# MCU.net
KiCad netlist of a schematic drawn in Altium Designer
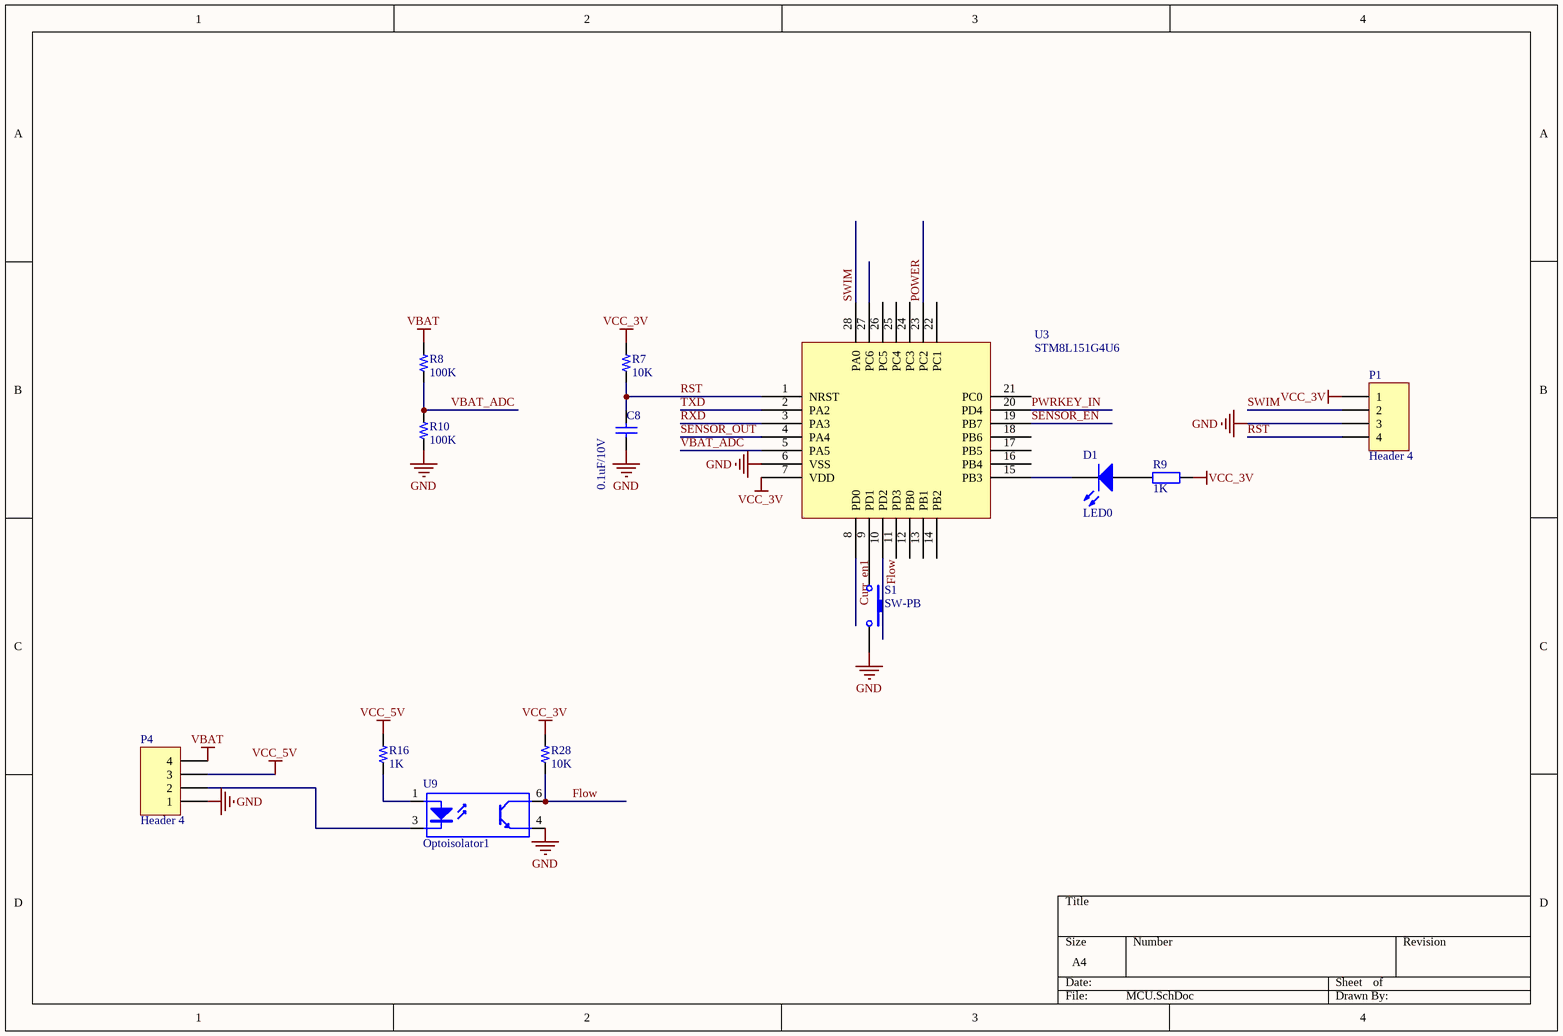
[diagram p0: MCU.SchDoc]

(export (version "E")
  (design (tool "Eeschema 10.0.6"))
  (components
    (comp (ref "C8")
      (value "0.1uF/10V")
      (footprint "0603C")
      (description "Capacitor")
      (fields (field (name "PUBLISHER") "Altium Limited"))
      (libsource (lib "Miscellaneous Devices") (part "Cap"))
    )
    (comp (ref "D1")
      (value "LED0")
      (footprint "0603LED")
      (description "Typical INFRARED GaAs LED")
      (fields (field (name "PUBLISHER") "Altium Limited"))
      (libsource (lib "Miscellaneous Devices") (part "LED0"))
    )
    (comp (ref "P1")
      (value "Header 4")
      (footprint "HDR1X4")
      (description "Header, 4-Pin")
      (fields (field (name "PUBLISHER") "Altium Limited"))
      (libsource (lib "") (part "Header 4_1"))
    )
    (comp (ref "P4")
      (value "Header 4")
      (footprint "HDR1X4")
      (description "Header, 4-Pin")
      (fields (field (name "PUBLISHER") "Altium Limited"))
      (libsource (lib "Miscellaneous Connectors") (part "Header 4"))
    )
    (comp (ref "R7") (value "10K") (footprint "0603R") (description "R") (libsource (lib "JRJ_1") (part "R")))
    (comp (ref "R8")
      (value "100K")
      (footprint "0603R")
      (description "R")
      (libsource (lib "JRJ_1") (part "R"))
    )
    (comp (ref "R9")
      (value "1K")
      (footprint "0603R")
      (description "Resistor")
      (fields (field (name "PUBLISHER") "Altium Limited"))
      (libsource (lib "Miscellaneous Devices") (part "Res2"))
    )
    (comp (ref "R10")
      (value "100K")
      (footprint "0603R")
      (description "R")
      (libsource (lib "JRJ_1") (part "R"))
    )
    (comp (ref "R16") (value "1K") (footprint "0603R") (description "R") (libsource (lib "JRJ_1") (part "R")))
    (comp (ref "R28")
      (value "10K")
      (footprint "0603R")
      (description "R")
      (libsource (lib "JRJ_1") (part "R"))
    )
    (comp (ref "S1")
      (value "SW-PB")
      (footprint "key")
      (description "Switch")
      (fields (field (name "PUBLISHER") "Altium Limited"))
      (libsource (lib "Miscellaneous Devices") (part "SW-PB"))
    )
    (comp (ref "U3")
      (value "STM8L151G4U6")
      (footprint "UFQFPN28")
      (libsource (lib "Schlib_20110825") (part "STM8L151G4U6"))
    )
    (comp (ref "U9")
      (value "Optoisolator1")
      (footprint "DIP-4")
      (description "4-Pin Phototransistor Optocoupler")
      (fields (field (name "PUBLISHER") "Altium Limited"))
      (libsource (lib "Miscellaneous Devices") (part "Optoisolator1"))
    )
  )
  (nets
    (net (code "1") (name "/Curr_en1") (class "Default")
      (node (ref "U3") (pin "8") (pinfunction "PD0_8") (pintype "passive"))
    )
    (net (code "2") (name "/Flow") (class "Default")
      (node (ref "R28") (pin "1") (pintype "passive"))
      (node (ref "U3") (pin "10") (pinfunction "PD2_10") (pintype "passive"))
      (node (ref "U9") (pin "6") (pinfunction "C_6") (pintype "passive"))
    )
    (net (code "3") (name "/POWER") (class "Default")
      (node (ref "U3") (pin "23") (pinfunction "PC2_23") (pintype "passive"))
    )
    (net (code "4") (name "/PWRKEY_IN") (class "Default")
      (node (ref "U3") (pin "20") (pinfunction "PD4_20") (pintype "passive"))
    )
    (net (code "5") (name "/RST") (class "Default")
      (node (ref "C8") (pin "1") (pinfunction "1_1") (pintype "passive"))
      (node (ref "P1") (pin "4") (pinfunction "4_4") (pintype "passive"))
      (node (ref "R7") (pin "1") (pintype "passive"))
      (node (ref "U3") (pin "1") (pinfunction "NRST_1") (pintype "passive"))
    )
    (net (code "6") (name "/RXD") (class "Default")
      (node (ref "U3") (pin "3") (pinfunction "PA3_3") (pintype "passive"))
    )
    (net (code "7") (name "/SENSOR_EN") (class "Default")
      (node (ref "U3") (pin "19") (pinfunction "PB7_19") (pintype "passive"))
    )
    (net (code "8") (name "/SENSOR_OUT") (class "Default")
      (node (ref "U3") (pin "4") (pinfunction "PA4_4") (pintype "passive"))
    )
    (net (code "9") (name "/SWIM") (class "Default")
      (node (ref "P1") (pin "2") (pinfunction "2_2") (pintype "passive"))
      (node (ref "U3") (pin "28") (pinfunction "PA0_28") (pintype "passive"))
    )
    (net (code "10") (name "/TXD") (class "Default")
      (node (ref "U3") (pin "2") (pinfunction "PA2_2") (pintype "passive"))
    )
    (net (code "11") (name "/VBAT_ADC") (class "Default")
      (node (ref "R10") (pin "2") (pintype "passive"))
      (node (ref "R8") (pin "1") (pintype "passive"))
      (node (ref "U3") (pin "5") (pinfunction "PA5_5") (pintype "passive"))
    )
    (net (code "12") (name "GND") (class "Default")
      (node (ref "C8") (pin "2") (pinfunction "2_2") (pintype "passive"))
      (node (ref "P1") (pin "3") (pinfunction "3_3") (pintype "passive"))
      (node (ref "P4") (pin "1") (pinfunction "1_1") (pintype "passive"))
      (node (ref "R10") (pin "1") (pintype "passive"))
      (node (ref "S1") (pin "2") (pinfunction "2_2") (pintype "passive"))
      (node (ref "U3") (pin "6") (pinfunction "VSS_6") (pintype "passive"))
      (node (ref "U9") (pin "4") (pinfunction "E_4") (pintype "passive"))
    )
    (net (code "13") (name "Net-(D1-A)") (class "Default")
      (node (ref "D1") (pin "1") (pinfunction "A_1") (pintype "passive"))
      (node (ref "R9") (pin "2") (pinfunction "2_2") (pintype "passive"))
    )
    (net (code "14") (name "Net-(D1-K)") (class "Default")
      (node (ref "D1") (pin "2") (pinfunction "K_2") (pintype "passive"))
      (node (ref "U3") (pin "15") (pinfunction "PB3_15") (pintype "passive"))
    )
    (net (code "15") (name "Net-(U3-PD1)") (class "Default")
      (node (ref "S1") (pin "1") (pinfunction "1_1") (pintype "passive"))
      (node (ref "U3") (pin "9") (pinfunction "PD1_9") (pintype "passive"))
    )
    (net (code "16") (name "Net-(U9-A)") (class "Default")
      (node (ref "R16") (pin "1") (pintype "passive"))
      (node (ref "U9") (pin "1") (pinfunction "A_1") (pintype "passive"))
    )
    (net (code "17") (name "Net-(U9-K)") (class "Default")
      (node (ref "P4") (pin "2") (pinfunction "2_2") (pintype "passive"))
      (node (ref "U9") (pin "3") (pinfunction "K_3") (pintype "passive"))
    )
    (net (code "18") (name "VBAT") (class "Default")
      (node (ref "P4") (pin "4") (pinfunction "4_4") (pintype "passive"))
      (node (ref "R8") (pin "2") (pintype "passive"))
    )
    (net (code "19") (name "VCC_3V") (class "Default")
      (node (ref "P1") (pin "1") (pinfunction "1_1") (pintype "passive"))
      (node (ref "R28") (pin "2") (pintype "passive"))
      (node (ref "R7") (pin "2") (pintype "passive"))
      (node (ref "R9") (pin "1") (pinfunction "1_1") (pintype "passive"))
      (node (ref "U3") (pin "7") (pinfunction "VDD_7") (pintype "passive"))
    )
    (net (code "20") (name "VCC_5V") (class "Default")
      (node (ref "P4") (pin "3") (pinfunction "3_3") (pintype "passive"))
      (node (ref "R16") (pin "2") (pintype "passive"))
    )
    (net (code "21") (name "unconnected-(U3-PB0-Pad12)") (class "Default")
      (node (ref "U3") (pin "12") (pinfunction "PB0_12") (pintype "passive"))
    )
    (net (code "22") (name "unconnected-(U3-PB1-Pad13)") (class "Default")
      (node (ref "U3") (pin "13") (pinfunction "PB1_13") (pintype "passive"))
    )
    (net (code "23") (name "unconnected-(U3-PB2-Pad14)") (class "Default")
      (node (ref "U3") (pin "14") (pinfunction "PB2_14") (pintype "passive"))
    )
    (net (code "24") (name "unconnected-(U3-PB4-Pad16)") (class "Default")
      (node (ref "U3") (pin "16") (pinfunction "PB4_16") (pintype "passive"))
    )
    (net (code "25") (name "unconnected-(U3-PB5-Pad17)") (class "Default")
      (node (ref "U3") (pin "17") (pinfunction "PB5_17") (pintype "passive"))
    )
    (net (code "26") (name "unconnected-(U3-PB6-Pad18)") (class "Default")
      (node (ref "U3") (pin "18") (pinfunction "PB6_18") (pintype "passive"))
    )
    (net (code "27") (name "unconnected-(U3-PC0-Pad21)") (class "Default")
      (node (ref "U3") (pin "21") (pinfunction "PC0_21") (pintype "passive"))
    )
    (net (code "28") (name "unconnected-(U3-PC1-Pad22)") (class "Default")
      (node (ref "U3") (pin "22") (pinfunction "PC1_22") (pintype "passive"))
    )
    (net (code "29") (name "unconnected-(U3-PC3-Pad24)") (class "Default")
      (node (ref "U3") (pin "24") (pinfunction "PC3_24") (pintype "passive"))
    )
    (net (code "30") (name "unconnected-(U3-PC4-Pad25)") (class "Default")
      (node (ref "U3") (pin "25") (pinfunction "PC4_25") (pintype "passive"))
    )
    (net (code "31") (name "unconnected-(U3-PC5-Pad26)") (class "Default")
      (node (ref "U3") (pin "26") (pinfunction "PC5_26") (pintype "passive"))
    )
    (net (code "32") (name "unconnected-(U3-PC6-Pad27)") (class "Default")
      (node (ref "U3") (pin "27") (pinfunction "PC6_27") (pintype "passive"))
    )
    (net (code "33") (name "unconnected-(U3-PD3-Pad11)") (class "Default")
      (node (ref "U3") (pin "11") (pinfunction "PD3_11") (pintype "passive"))
    )
  )
)
